# motor_subsheet_1.net
KiCad netlist of a schematic drawn in Altium Designer
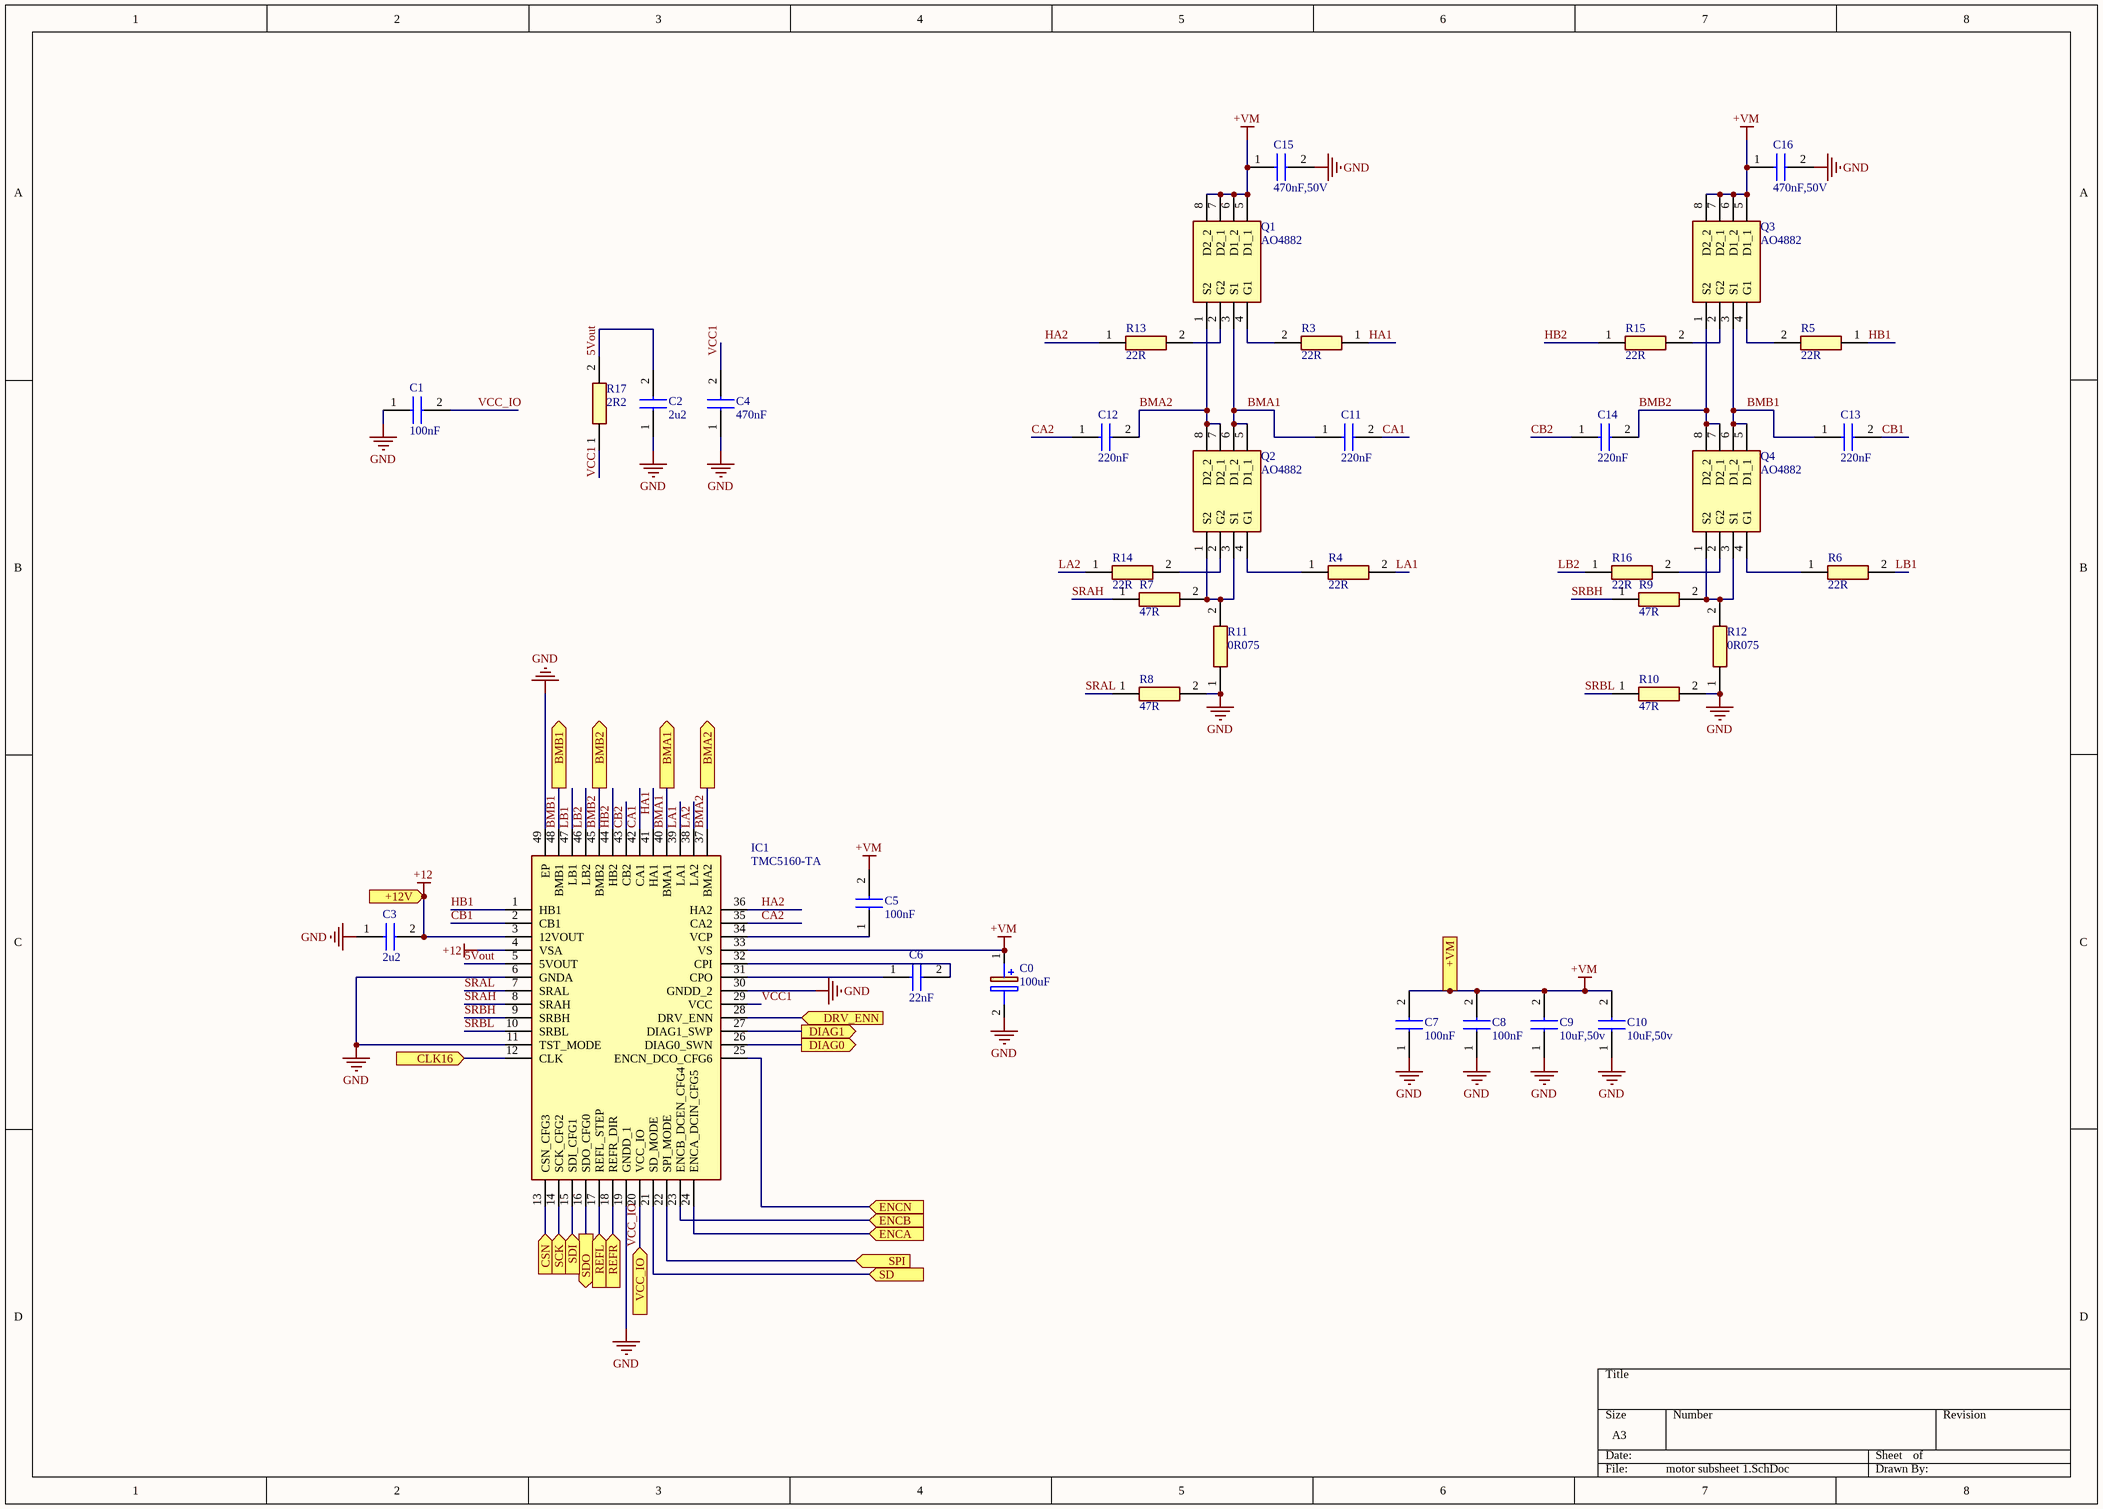
[diagram p0: motor subsheet 1.SchDoc]

(export (version "E")
  (design (tool "Eeschema 10.0.6"))
  (components
    (comp (ref "C0")
      (value "100uF")
      (footprint "SamacSys:CAPAE850X1050N")
      (description "Capacitor Polarised\r\nMAL215097011E3")
      (fields
        (field (name "MANUFACTURER_PART_NUMBER") "MAL215097011E3")
        (field (name "MOUSER PART NUMBER") "594-MAL215097011E3")
      )
      (libsource (lib "*") (part "MAL215097011E3"))
    )
    (comp (ref "C1")
      (value "100nF")
      (footprint "SamacSys:CAPC1608X90N")
      (description "Capacitor")
      (fields
        (field (name "MANUFACTURER_PART_NUMBER") "GCM188R71H224KA64D")
        (field (name "MOUSER PART NUMBER") "81-GCM188R71H224K64D")
      )
      (libsource (lib "*") (part "GCM188R71H224KA64D"))
    )
    (comp (ref "C2")
      (value "2u2")
      (footprint "SamacSys:CAPC1608X90N")
      (description "Capacitor")
      (fields
        (field (name "MANUFACTURER_PART_NUMBER") "GCM188R71H224KA64D")
        (field (name "MOUSER PART NUMBER") "81-GCM188R71H224K64D")
      )
      (libsource (lib "*") (part "GCM188R71H224KA64D"))
    )
    (comp (ref "C3")
      (value "2u2")
      (footprint "SamacSys:CAPC1608X90N")
      (description "Capacitor")
      (fields
        (field (name "MANUFACTURER_PART_NUMBER") "GCM188R71H224KA64D")
        (field (name "MOUSER PART NUMBER") "81-GCM188R71H224K64D")
      )
      (libsource (lib "*") (part "GCM188R71H224KA64D"))
    )
    (comp (ref "C4")
      (value "470nF")
      (footprint "SamacSys:CAPC1608X90N")
      (description "Capacitor")
      (fields
        (field (name "MANUFACTURER_PART_NUMBER") "GCM188R71H224KA64D")
        (field (name "MOUSER PART NUMBER") "81-GCM188R71H224K64D")
      )
      (libsource (lib "*") (part "GCM188R71H224KA64D"))
    )
    (comp (ref "C5")
      (value "100nF")
      (footprint "SamacSys:CAPC1608X90N")
      (description "Capacitor")
      (fields
        (field (name "MANUFACTURER_PART_NUMBER") "GCM188R71H224KA64D")
        (field (name "MOUSER PART NUMBER") "81-GCM188R71H224K64D")
      )
      (libsource (lib "*") (part "GCM188R71H224KA64D"))
    )
    (comp (ref "C6")
      (value "22nF")
      (footprint "SamacSys:CAPC1608X90N")
      (description "Capacitor")
      (fields
        (field (name "MANUFACTURER_PART_NUMBER") "GCM188R71H224KA64D")
        (field (name "MOUSER PART NUMBER") "81-GCM188R71H224K64D")
      )
      (libsource (lib "*") (part "GCM188R71H224KA64D"))
    )
    (comp (ref "C7")
      (value "100nF")
      (footprint "SamacSys:CAPC1608X90N")
      (description "Capacitor")
      (fields
        (field (name "MANUFACTURER_PART_NUMBER") "GCM188R71H224KA64D")
        (field (name "MOUSER PART NUMBER") "81-GCM188R71H224K64D")
      )
      (libsource (lib "*") (part "GCM188R71H224KA64D"))
    )
    (comp (ref "C8")
      (value "100nF")
      (footprint "SamacSys:CAPC1608X90N")
      (description "Capacitor")
      (fields
        (field (name "MANUFACTURER_PART_NUMBER") "GCM188R71H224KA64D")
        (field (name "MOUSER PART NUMBER") "81-GCM188R71H224K64D")
      )
      (libsource (lib "*") (part "GCM188R71H224KA64D"))
    )
    (comp (ref "C9")
      (value "10uF,50v")
      (footprint "SamacSys:CAPC3216X180N")
      (description "Capacitor")
      (fields
        (field (name "MANUFACTURER_PART_NUMBER") "GRM31CR61H106MA12L")
        (field (name "MOUSER PART NUMBER") "81-GRM31CR61H106MA2L")
      )
      (libsource (lib "*") (part "GRM31CR61H106MA12L"))
    )
    (comp (ref "C10")
      (value "10uF,50v")
      (footprint "SamacSys:CAPC3216X180N")
      (description "Capacitor")
      (fields
        (field (name "MANUFACTURER_PART_NUMBER") "GRM31CR61H106MA12L")
        (field (name "MOUSER PART NUMBER") "81-GRM31CR61H106MA2L")
      )
      (libsource (lib "*") (part "GRM31CR61H106MA12L"))
    )
    (comp (ref "C11")
      (value "220nF")
      (footprint "SamacSys:CAPC1608X90N")
      (description "Capacitor")
      (fields
        (field (name "MANUFACTURER_PART_NUMBER") "GCM188R71H224KA64D")
        (field (name "MOUSER PART NUMBER") "81-GCM188R71H224K64D")
      )
      (libsource (lib "*") (part "GCM188R71H224KA64D"))
    )
    (comp (ref "C12")
      (value "220nF")
      (footprint "SamacSys:CAPC1608X90N")
      (description "Capacitor")
      (fields
        (field (name "MANUFACTURER_PART_NUMBER") "GCM188R71H224KA64D")
        (field (name "MOUSER PART NUMBER") "81-GCM188R71H224K64D")
      )
      (libsource (lib "*") (part "GCM188R71H224KA64D"))
    )
    (comp (ref "C13")
      (value "220nF")
      (footprint "SamacSys:CAPC1608X90N")
      (description "Capacitor")
      (fields
        (field (name "MANUFACTURER_PART_NUMBER") "GCM188R71H224KA64D")
        (field (name "MOUSER PART NUMBER") "81-GCM188R71H224K64D")
      )
      (libsource (lib "*") (part "GCM188R71H224KA64D"))
    )
    (comp (ref "C14")
      (value "220nF")
      (footprint "SamacSys:CAPC1608X90N")
      (description "Capacitor")
      (fields
        (field (name "MANUFACTURER_PART_NUMBER") "GCM188R71H224KA64D")
        (field (name "MOUSER PART NUMBER") "81-GCM188R71H224K64D")
      )
      (libsource (lib "*") (part "GCM188R71H224KA64D"))
    )
    (comp (ref "C15")
      (value "470nF,50V")
      (footprint "SamacSys:C1608_Commercial")
      (description "Capacitor")
      (fields
        (field (name "MANUFACTURER_PART_NUMBER") "C1608X7R1H474K080AC")
        (field (name "MOUSER PART NUMBER") "810-C1608X7R1H474K")
      )
      (libsource (lib "*") (part "C1608X7R1H474K080AC"))
    )
    (comp (ref "C16")
      (value "470nF,50V")
      (footprint "SamacSys:C1608_Commercial")
      (description "Capacitor")
      (fields
        (field (name "MANUFACTURER_PART_NUMBER") "C1608X7R1H474K080AC")
        (field (name "MOUSER PART NUMBER") "810-C1608X7R1H474K")
      )
      (libsource (lib "*") (part "C1608X7R1H474K080AC"))
    )
    (comp (ref "IC1")
      (value "TMC5160-TA")
      (footprint "SamacSys:QFP50P900X900X120-49N")
      (description "Integrated Circuit")
      (fields (field (name "LCSC PART #") "C516354"))
      (libsource (lib "*") (part "TMC5160-TA"))
    )
    (comp (ref "Q1")
      (value "AO4882")
      (footprint "SamacSys:SOIC127P600X175-8N")
      (description "MOSFET (N-Channel)")
      (fields (field (name "LCSC PART #") "C3040598"))
      (libsource (lib "*") (part "AO4882"))
    )
    (comp (ref "Q2")
      (value "AO4882")
      (footprint "SamacSys:SOIC127P600X175-8N")
      (description "MOSFET (N-Channel)")
      (fields (field (name "LCSC PART #") "C3040598"))
      (libsource (lib "*") (part "AO4882"))
    )
    (comp (ref "Q3")
      (value "AO4882")
      (footprint "SamacSys:SOIC127P600X175-8N")
      (description "MOSFET (N-Channel)")
      (fields (field (name "LCSC PART #") "C3040598"))
      (libsource (lib "*") (part "AO4882"))
    )
    (comp (ref "Q4")
      (value "AO4882")
      (footprint "SamacSys:SOIC127P600X175-8N")
      (description "MOSFET (N-Channel)")
      (fields (field (name "LCSC PART #") "C3040598"))
      (libsource (lib "*") (part "AO4882"))
    )
    (comp (ref "R3")
      (value "22R")
      (footprint "SamacSys:RESC1608X55N")
      (description "Resistor")
      (fields
        (field (name "MANUFACTURER_PART_NUMBER") "MC0063W06031100K")
        (field (name "LCSC PART #") "C122707")
      )
      (libsource (lib "") (part "MC0063W06031100K_1"))
    )
    (comp (ref "R4")
      (value "22R")
      (footprint "SamacSys:RESC1608X55N")
      (description "Resistor")
      (fields
        (field (name "MANUFACTURER_PART_NUMBER") "MC0063W06031100K")
        (field (name "LCSC PART #") "C122707")
      )
      (libsource (lib "*") (part "MC0063W06031100K"))
    )
    (comp (ref "R5")
      (value "22R")
      (footprint "SamacSys:RESC1608X55N")
      (description "Resistor")
      (fields
        (field (name "MANUFACTURER_PART_NUMBER") "MC0063W06031100K")
        (field (name "LCSC PART #") "C122707")
      )
      (libsource (lib "") (part "MC0063W06031100K_1"))
    )
    (comp (ref "R6")
      (value "22R")
      (footprint "SamacSys:RESC1608X55N")
      (description "Resistor")
      (fields
        (field (name "MANUFACTURER_PART_NUMBER") "MC0063W06031100K")
        (field (name "LCSC PART #") "C122707")
      )
      (libsource (lib "*") (part "MC0063W06031100K"))
    )
    (comp (ref "R7")
      (value "47R")
      (footprint "SamacSys:RESC1608X60N")
      (description "Resistor")
      (fields
        (field (name "MANUFACTURER_PART_NUMBER") "MCSR06X47R0FTL")
        (field (name "LCSC PART #") "C2136913")
      )
      (libsource (lib "*") (part "MCSR06X47R0FTL"))
    )
    (comp (ref "R8")
      (value "47R")
      (footprint "SamacSys:RESC1608X60N")
      (description "Resistor")
      (fields
        (field (name "MANUFACTURER_PART_NUMBER") "MCSR06X47R0FTL")
        (field (name "LCSC PART #") "C2136913")
      )
      (libsource (lib "*") (part "MCSR06X47R0FTL"))
    )
    (comp (ref "R9")
      (value "47R")
      (footprint "SamacSys:RESC1608X60N")
      (description "Resistor")
      (fields
        (field (name "MANUFACTURER_PART_NUMBER") "MCSR06X47R0FTL")
        (field (name "LCSC PART #") "C2136913")
      )
      (libsource (lib "*") (part "MCSR06X47R0FTL"))
    )
    (comp (ref "R10")
      (value "47R")
      (footprint "SamacSys:RESC1608X60N")
      (description "Resistor")
      (fields
        (field (name "MANUFACTURER_PART_NUMBER") "MCSR06X47R0FTL")
        (field (name "LCSC PART #") "C2136913")
      )
      (libsource (lib "*") (part "MCSR06X47R0FTL"))
    )
    (comp (ref "R11")
      (value "0R075")
      (footprint "SamacSys:ERJ8_B_BW_R_LW_CW_D")
      (description "Resistor")
      (fields
        (field (name "MANUFACTURER_PART_NUMBER") "ERJ-8BWFR075V")
        (field (name "MOUSER PART NUMBER") "667-ERJ-8BWFR075V")
      )
      (libsource (lib "*") (part "ERJ-8BWFR075V"))
    )
    (comp (ref "R12")
      (value "0R075")
      (footprint "SamacSys:ERJ8_B_BW_R_LW_CW_D")
      (description "Resistor")
      (fields
        (field (name "MANUFACTURER_PART_NUMBER") "ERJ-8BWFR075V")
        (field (name "MOUSER PART NUMBER") "667-ERJ-8BWFR075V")
      )
      (libsource (lib "*") (part "ERJ-8BWFR075V"))
    )
    (comp (ref "R13")
      (value "22R")
      (footprint "SamacSys:RESC1608X55N")
      (description "Resistor")
      (fields
        (field (name "MANUFACTURER_PART_NUMBER") "MC0063W06031100K")
        (field (name "LCSC PART #") "C122707")
      )
      (libsource (lib "*") (part "MC0063W06031100K"))
    )
    (comp (ref "R14")
      (value "22R")
      (footprint "SamacSys:RESC1608X55N")
      (description "Resistor")
      (fields
        (field (name "MANUFACTURER_PART_NUMBER") "MC0063W06031100K")
        (field (name "LCSC PART #") "C122707")
      )
      (libsource (lib "*") (part "MC0063W06031100K"))
    )
    (comp (ref "R15")
      (value "22R")
      (footprint "SamacSys:RESC1608X55N")
      (description "Resistor")
      (fields
        (field (name "MANUFACTURER_PART_NUMBER") "MC0063W06031100K")
        (field (name "LCSC PART #") "C122707")
      )
      (libsource (lib "*") (part "MC0063W06031100K"))
    )
    (comp (ref "R16")
      (value "22R")
      (footprint "SamacSys:RESC1608X55N")
      (description "Resistor")
      (fields
        (field (name "MANUFACTURER_PART_NUMBER") "MC0063W06031100K")
        (field (name "LCSC PART #") "C122707")
      )
      (libsource (lib "*") (part "MC0063W06031100K"))
    )
    (comp (ref "R17")
      (value "2R2")
      (footprint "SamacSys:RESC1608X55N")
      (description "Resistor")
      (fields
        (field (name "MANUFACTURER_PART_NUMBER") "MC0063W06031100K")
        (field (name "LCSC PART #") "C269422")
      )
      (libsource (lib "") (part "MC0063W06031100K_2"))
    )
  )
  (nets
    (net (code "1") (name "+12") (class "Default")
      (node (ref "C3") (pin "2") (pinfunction "2_2") (pintype "passive"))
      (node (ref "IC1") (pin "3") (pinfunction "12VOUT_3") (pintype "passive"))
      (node (ref "IC1") (pin "4") (pinfunction "VSA_4") (pintype "passive"))
    )
    (net (code "2") (name "+VM") (class "Default")
      (node (ref "C0") (pin "1") (pinfunction "+_1") (pintype "passive"))
      (node (ref "C10") (pin "2") (pinfunction "2_2") (pintype "passive"))
      (node (ref "C15") (pin "1") (pinfunction "1_1") (pintype "passive"))
      (node (ref "C16") (pin "1") (pinfunction "1_1") (pintype "passive"))
      (node (ref "C5") (pin "2") (pinfunction "2_2") (pintype "passive"))
      (node (ref "C7") (pin "2") (pinfunction "2_2") (pintype "passive"))
      (node (ref "C8") (pin "2") (pinfunction "2_2") (pintype "passive"))
      (node (ref "C9") (pin "2") (pinfunction "2_2") (pintype "passive"))
      (node (ref "IC1") (pin "33") (pinfunction "VS_33") (pintype "passive"))
      (node (ref "Q1") (pin "5") (pinfunction "D1_1_5") (pintype "passive"))
      (node (ref "Q1") (pin "6") (pinfunction "D1_2_6") (pintype "passive"))
      (node (ref "Q1") (pin "7") (pinfunction "D2_1_7") (pintype "passive"))
      (node (ref "Q1") (pin "8") (pinfunction "D2_2_8") (pintype "passive"))
      (node (ref "Q3") (pin "5") (pinfunction "D1_1_5") (pintype "passive"))
      (node (ref "Q3") (pin "6") (pinfunction "D1_2_6") (pintype "passive"))
      (node (ref "Q3") (pin "7") (pinfunction "D2_1_7") (pintype "passive"))
      (node (ref "Q3") (pin "8") (pinfunction "D2_2_8") (pintype "passive"))
    )
    (net (code "3") (name "/5Vout") (class "Default")
      (node (ref "C2") (pin "2") (pinfunction "2_2") (pintype "passive"))
      (node (ref "IC1") (pin "5") (pinfunction "5VOUT_5") (pintype "passive"))
      (node (ref "R17") (pin "2") (pinfunction "2_2") (pintype "passive"))
    )
    (net (code "4") (name "/BMA1") (class "Default")
      (node (ref "C11") (pin "1") (pinfunction "1_1") (pintype "passive"))
      (node (ref "IC1") (pin "40") (pinfunction "BMA1_40") (pintype "passive"))
      (node (ref "Q1") (pin "3") (pinfunction "S1_3") (pintype "passive"))
      (node (ref "Q2") (pin "5") (pinfunction "D1_1_5") (pintype "passive"))
      (node (ref "Q2") (pin "6") (pinfunction "D1_2_6") (pintype "passive"))
    )
    (net (code "5") (name "/BMA2") (class "Default")
      (node (ref "C12") (pin "2") (pinfunction "2_2") (pintype "passive"))
      (node (ref "IC1") (pin "37") (pinfunction "BMA2_37") (pintype "passive"))
      (node (ref "Q1") (pin "1") (pinfunction "S2_1") (pintype "passive"))
      (node (ref "Q2") (pin "7") (pinfunction "D2_1_7") (pintype "passive"))
      (node (ref "Q2") (pin "8") (pinfunction "D2_2_8") (pintype "passive"))
    )
    (net (code "6") (name "/BMB1") (class "Default")
      (node (ref "C13") (pin "1") (pinfunction "1_1") (pintype "passive"))
      (node (ref "IC1") (pin "48") (pinfunction "BMB1_48") (pintype "passive"))
      (node (ref "Q3") (pin "3") (pinfunction "S1_3") (pintype "passive"))
      (node (ref "Q4") (pin "5") (pinfunction "D1_1_5") (pintype "passive"))
      (node (ref "Q4") (pin "6") (pinfunction "D1_2_6") (pintype "passive"))
    )
    (net (code "7") (name "/BMB2") (class "Default")
      (node (ref "C14") (pin "2") (pinfunction "2_2") (pintype "passive"))
      (node (ref "IC1") (pin "45") (pinfunction "BMB2_45") (pintype "passive"))
      (node (ref "Q3") (pin "1") (pinfunction "S2_1") (pintype "passive"))
      (node (ref "Q4") (pin "7") (pinfunction "D2_1_7") (pintype "passive"))
      (node (ref "Q4") (pin "8") (pinfunction "D2_2_8") (pintype "passive"))
    )
    (net (code "8") (name "/CA1") (class "Default")
      (node (ref "C11") (pin "2") (pinfunction "2_2") (pintype "passive"))
      (node (ref "IC1") (pin "42") (pinfunction "CA1_42") (pintype "passive"))
    )
    (net (code "9") (name "/CA2") (class "Default")
      (node (ref "C12") (pin "1") (pinfunction "1_1") (pintype "passive"))
      (node (ref "IC1") (pin "35") (pinfunction "CA2_35") (pintype "passive"))
    )
    (net (code "10") (name "/CB1") (class "Default")
      (node (ref "C13") (pin "2") (pinfunction "2_2") (pintype "passive"))
      (node (ref "IC1") (pin "2") (pinfunction "CB1_2") (pintype "passive"))
    )
    (net (code "11") (name "/CB2") (class "Default")
      (node (ref "C14") (pin "1") (pinfunction "1_1") (pintype "passive"))
      (node (ref "IC1") (pin "43") (pinfunction "CB2_43") (pintype "passive"))
    )
    (net (code "12") (name "/CLK16") (class "Default")
      (node (ref "IC1") (pin "12") (pinfunction "CLK_12") (pintype "passive"))
    )
    (net (code "13") (name "/CSN") (class "Default")
      (node (ref "IC1") (pin "13") (pinfunction "CSN_CFG3_13") (pintype "passive"))
    )
    (net (code "14") (name "/DIAG0") (class "Default")
      (node (ref "IC1") (pin "26") (pinfunction "DIAG0_SWN_26") (pintype "passive"))
    )
    (net (code "15") (name "/DIAG1") (class "Default")
      (node (ref "IC1") (pin "27") (pinfunction "DIAG1_SWP_27") (pintype "passive"))
    )
    (net (code "16") (name "/DRV_ENN") (class "Default")
      (node (ref "IC1") (pin "28") (pinfunction "DRV_ENN_28") (pintype "passive"))
    )
    (net (code "17") (name "/ENCA") (class "Default")
      (node (ref "IC1") (pin "24") (pinfunction "ENCA_DCIN_CFG5_24") (pintype "passive"))
    )
    (net (code "18") (name "/ENCB") (class "Default")
      (node (ref "IC1") (pin "23") (pinfunction "ENCB_DCEN_CFG4_23") (pintype "passive"))
    )
    (net (code "19") (name "/ENCN") (class "Default")
      (node (ref "IC1") (pin "25") (pinfunction "ENCN_DCO_CFG6_25") (pintype "passive"))
    )
    (net (code "20") (name "/HA1") (class "Default")
      (node (ref "IC1") (pin "41") (pinfunction "HA1_41") (pintype "passive"))
      (node (ref "R3") (pin "1") (pinfunction "1_1") (pintype "passive"))
    )
    (net (code "21") (name "/HA2") (class "Default")
      (node (ref "IC1") (pin "36") (pinfunction "HA2_36") (pintype "passive"))
      (node (ref "R13") (pin "1") (pinfunction "1_1") (pintype "passive"))
    )
    (net (code "22") (name "/HB1") (class "Default")
      (node (ref "IC1") (pin "1") (pinfunction "HB1_1") (pintype "passive"))
      (node (ref "R5") (pin "1") (pinfunction "1_1") (pintype "passive"))
    )
    (net (code "23") (name "/HB2") (class "Default")
      (node (ref "IC1") (pin "44") (pinfunction "HB2_44") (pintype "passive"))
      (node (ref "R15") (pin "1") (pinfunction "1_1") (pintype "passive"))
    )
    (net (code "24") (name "/LA1") (class "Default")
      (node (ref "IC1") (pin "39") (pinfunction "LA1_39") (pintype "passive"))
      (node (ref "R4") (pin "2") (pinfunction "2_2") (pintype "passive"))
    )
    (net (code "25") (name "/LA2") (class "Default")
      (node (ref "IC1") (pin "38") (pinfunction "LA2_38") (pintype "passive"))
      (node (ref "R14") (pin "1") (pinfunction "1_1") (pintype "passive"))
    )
    (net (code "26") (name "/LB1") (class "Default")
      (node (ref "IC1") (pin "47") (pinfunction "LB1_47") (pintype "passive"))
      (node (ref "R6") (pin "2") (pinfunction "2_2") (pintype "passive"))
    )
    (net (code "27") (name "/LB2") (class "Default")
      (node (ref "IC1") (pin "46") (pinfunction "LB2_46") (pintype "passive"))
      (node (ref "R16") (pin "1") (pinfunction "1_1") (pintype "passive"))
    )
    (net (code "28") (name "/REFL") (class "Default")
      (node (ref "IC1") (pin "17") (pinfunction "REFL_STEP_17") (pintype "passive"))
    )
    (net (code "29") (name "/REFR") (class "Default")
      (node (ref "IC1") (pin "18") (pinfunction "REFR_DIR_18") (pintype "passive"))
    )
    (net (code "30") (name "/SCK") (class "Default")
      (node (ref "IC1") (pin "14") (pinfunction "SCK_CFG2_14") (pintype "passive"))
    )
    (net (code "31") (name "/SD") (class "Default")
      (node (ref "IC1") (pin "21") (pinfunction "SD_MODE_21") (pintype "passive"))
    )
    (net (code "32") (name "/SDI") (class "Default")
      (node (ref "IC1") (pin "15") (pinfunction "SDI_CFG1_15") (pintype "passive"))
    )
    (net (code "33") (name "/SDO") (class "Default")
      (node (ref "IC1") (pin "16") (pinfunction "SDO_CFG0_16") (pintype "passive"))
    )
    (net (code "34") (name "/SPI") (class "Default")
      (node (ref "IC1") (pin "22") (pinfunction "SPI_MODE_22") (pintype "passive"))
    )
    (net (code "35") (name "/SRAH") (class "Default")
      (node (ref "IC1") (pin "8") (pinfunction "SRAH_8") (pintype "passive"))
      (node (ref "R7") (pin "1") (pinfunction "1_1") (pintype "passive"))
    )
    (net (code "36") (name "/SRAL") (class "Default")
      (node (ref "IC1") (pin "7") (pinfunction "SRAL_7") (pintype "passive"))
      (node (ref "R8") (pin "1") (pinfunction "1_1") (pintype "passive"))
    )
    (net (code "37") (name "/SRBH") (class "Default")
      (node (ref "IC1") (pin "9") (pinfunction "SRBH_9") (pintype "passive"))
      (node (ref "R9") (pin "1") (pinfunction "1_1") (pintype "passive"))
    )
    (net (code "38") (name "/SRBL") (class "Default")
      (node (ref "IC1") (pin "10") (pinfunction "SRBL_10") (pintype "passive"))
      (node (ref "R10") (pin "1") (pinfunction "1_1") (pintype "passive"))
    )
    (net (code "39") (name "/VCC1") (class "Default")
      (node (ref "C4") (pin "2") (pinfunction "2_2") (pintype "passive"))
      (node (ref "IC1") (pin "29") (pinfunction "VCC_29") (pintype "passive"))
      (node (ref "R17") (pin "1") (pinfunction "1_1") (pintype "passive"))
    )
    (net (code "40") (name "/VCC_IO") (class "Default")
      (node (ref "C1") (pin "2") (pinfunction "2_2") (pintype "passive"))
      (node (ref "IC1") (pin "20") (pinfunction "VCC_IO_20") (pintype "passive"))
    )
    (net (code "41") (name "GND") (class "Default")
      (node (ref "C0") (pin "2") (pinfunction "-_2") (pintype "passive"))
      (node (ref "C1") (pin "1") (pinfunction "1_1") (pintype "passive"))
      (node (ref "C10") (pin "1") (pinfunction "1_1") (pintype "passive"))
      (node (ref "C15") (pin "2") (pinfunction "2_2") (pintype "passive"))
      (node (ref "C16") (pin "2") (pinfunction "2_2") (pintype "passive"))
      (node (ref "C2") (pin "1") (pinfunction "1_1") (pintype "passive"))
      (node (ref "C3") (pin "1") (pinfunction "1_1") (pintype "passive"))
      (node (ref "C4") (pin "1") (pinfunction "1_1") (pintype "passive"))
      (node (ref "C7") (pin "1") (pinfunction "1_1") (pintype "passive"))
      (node (ref "C8") (pin "1") (pinfunction "1_1") (pintype "passive"))
      (node (ref "C9") (pin "1") (pinfunction "1_1") (pintype "passive"))
      (node (ref "IC1") (pin "11") (pinfunction "TST_MODE_11") (pintype "passive"))
      (node (ref "IC1") (pin "19") (pinfunction "GNDD_1_19") (pintype "passive"))
      (node (ref "IC1") (pin "30") (pinfunction "GNDD_2_30") (pintype "passive"))
      (node (ref "IC1") (pin "49") (pinfunction "EP_49") (pintype "passive"))
      (node (ref "IC1") (pin "6") (pinfunction "GNDA_6") (pintype "passive"))
      (node (ref "R10") (pin "2") (pinfunction "2_2") (pintype "passive"))
      (node (ref "R11") (pin "1") (pinfunction "1_1") (pintype "passive"))
      (node (ref "R12") (pin "1") (pinfunction "1_1") (pintype "passive"))
      (node (ref "R8") (pin "2") (pinfunction "2_2") (pintype "passive"))
    )
    (net (code "42") (name "Net-(IC1-CPI)") (class "Default")
      (node (ref "C6") (pin "2") (pinfunction "2_2") (pintype "passive"))
      (node (ref "IC1") (pin "32") (pinfunction "CPI_32") (pintype "passive"))
    )
    (net (code "43") (name "Net-(IC1-CPO)") (class "Default")
      (node (ref "C6") (pin "1") (pinfunction "1_1") (pintype "passive"))
      (node (ref "IC1") (pin "31") (pinfunction "CPO_31") (pintype "passive"))
    )
    (net (code "44") (name "Net-(IC1-VCP)") (class "Default")
      (node (ref "C5") (pin "1") (pinfunction "1_1") (pintype "passive"))
      (node (ref "IC1") (pin "34") (pinfunction "VCP_34") (pintype "passive"))
    )
    (net (code "45") (name "Net-(Q1-G1)") (class "Default")
      (node (ref "Q1") (pin "4") (pinfunction "G1_4") (pintype "passive"))
      (node (ref "R3") (pin "2") (pinfunction "2_2") (pintype "passive"))
    )
    (net (code "46") (name "Net-(Q1-G2)") (class "Default")
      (node (ref "Q1") (pin "2") (pinfunction "G2_2") (pintype "passive"))
      (node (ref "R13") (pin "2") (pinfunction "2_2") (pintype "passive"))
    )
    (net (code "47") (name "Net-(Q2-G1)") (class "Default")
      (node (ref "Q2") (pin "4") (pinfunction "G1_4") (pintype "passive"))
      (node (ref "R4") (pin "1") (pinfunction "1_1") (pintype "passive"))
    )
    (net (code "48") (name "Net-(Q2-G2)") (class "Default")
      (node (ref "Q2") (pin "2") (pinfunction "G2_2") (pintype "passive"))
      (node (ref "R14") (pin "2") (pinfunction "2_2") (pintype "passive"))
    )
    (net (code "49") (name "Net-(Q2-S1)") (class "Default")
      (node (ref "Q2") (pin "1") (pinfunction "S2_1") (pintype "passive"))
      (node (ref "Q2") (pin "3") (pinfunction "S1_3") (pintype "passive"))
      (node (ref "R11") (pin "2") (pinfunction "2_2") (pintype "passive"))
      (node (ref "R7") (pin "2") (pinfunction "2_2") (pintype "passive"))
    )
    (net (code "50") (name "Net-(Q3-G1)") (class "Default")
      (node (ref "Q3") (pin "4") (pinfunction "G1_4") (pintype "passive"))
      (node (ref "R5") (pin "2") (pinfunction "2_2") (pintype "passive"))
    )
    (net (code "51") (name "Net-(Q3-G2)") (class "Default")
      (node (ref "Q3") (pin "2") (pinfunction "G2_2") (pintype "passive"))
      (node (ref "R15") (pin "2") (pinfunction "2_2") (pintype "passive"))
    )
    (net (code "52") (name "Net-(Q4-G1)") (class "Default")
      (node (ref "Q4") (pin "4") (pinfunction "G1_4") (pintype "passive"))
      (node (ref "R6") (pin "1") (pinfunction "1_1") (pintype "passive"))
    )
    (net (code "53") (name "Net-(Q4-G2)") (class "Default")
      (node (ref "Q4") (pin "2") (pinfunction "G2_2") (pintype "passive"))
      (node (ref "R16") (pin "2") (pinfunction "2_2") (pintype "passive"))
    )
    (net (code "54") (name "Net-(Q4-S1)") (class "Default")
      (node (ref "Q4") (pin "1") (pinfunction "S2_1") (pintype "passive"))
      (node (ref "Q4") (pin "3") (pinfunction "S1_3") (pintype "passive"))
      (node (ref "R12") (pin "2") (pinfunction "2_2") (pintype "passive"))
      (node (ref "R9") (pin "2") (pinfunction "2_2") (pintype "passive"))
    )
  )
)
